# butter-test.net
KiCad netlist of a schematic drawn in EAGLE
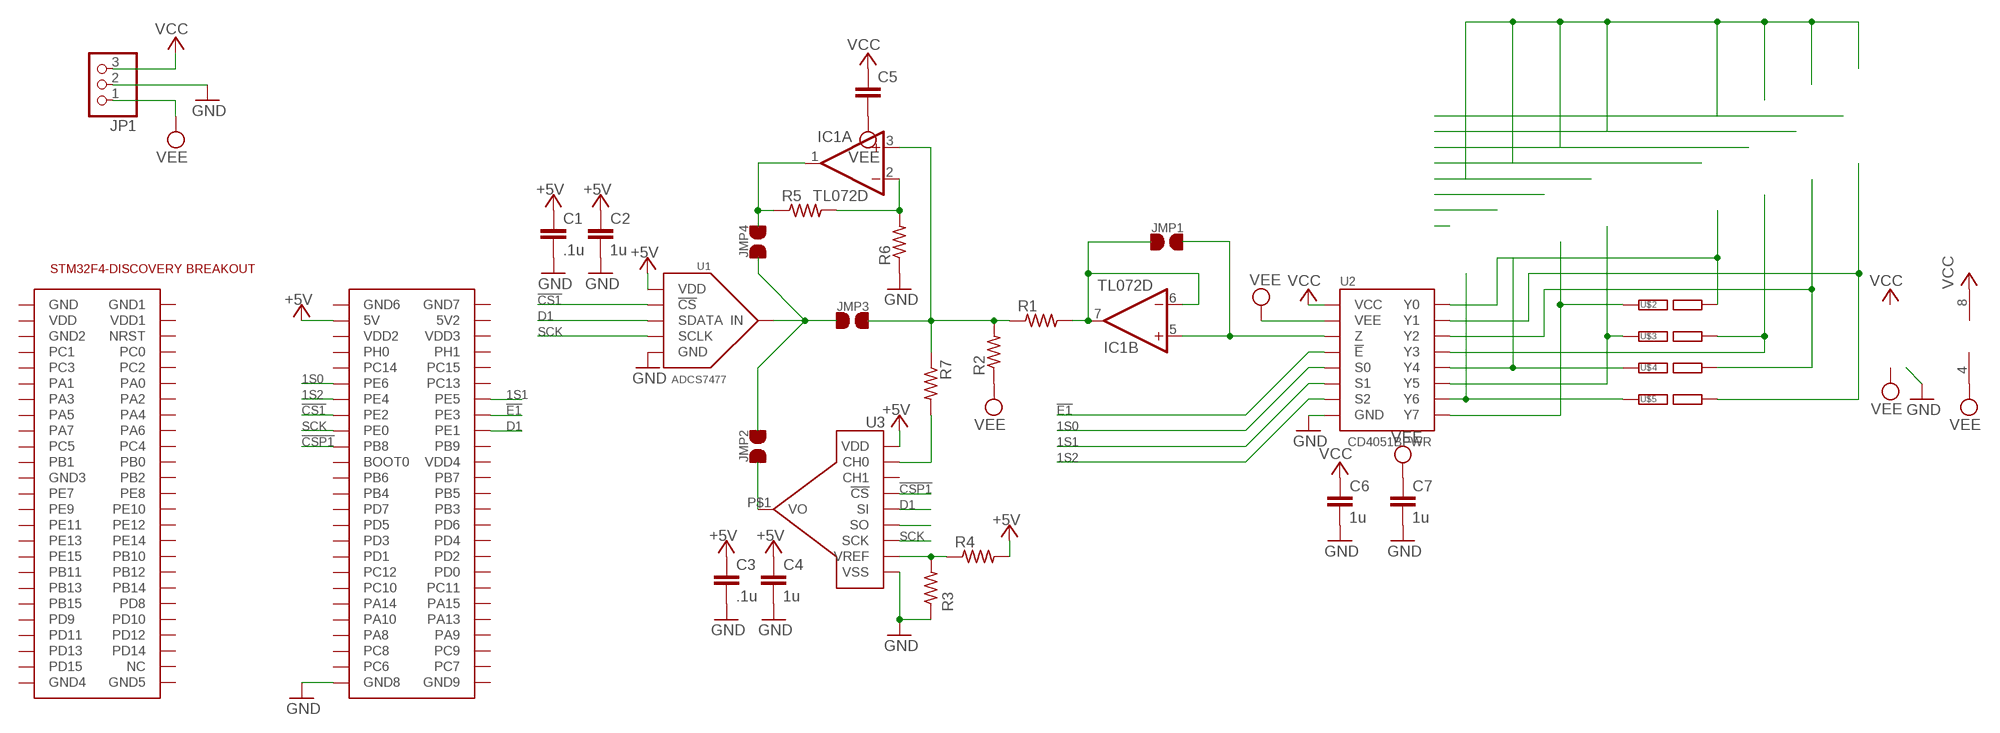
[diagram p0: schematic, sheet 1]

(export (version "E")
  (design (tool "Eeschema 10.0.6"))
  (components
    (comp (ref "C1")
      (value ".1u")
      (footprint "eagle-import:C0805")
      (libsource (lib "eagle-import") (part "C-EUC0805"))
    )
    (comp (ref "C2")
      (value "1u")
      (footprint "eagle-import:C0805")
      (libsource (lib "eagle-import") (part "C-EUC0805"))
    )
    (comp (ref "C3")
      (value ".1u")
      (footprint "eagle-import:C0805")
      (libsource (lib "eagle-import") (part "C-EUC0805"))
    )
    (comp (ref "C4")
      (value "1u")
      (footprint "eagle-import:C0805")
      (libsource (lib "eagle-import") (part "C-EUC0805"))
    )
    (comp (ref "C5")
      (value "C-EUC0805")
      (footprint "eagle-import:C0805")
      (libsource (lib "eagle-import") (part "C-EUC0805"))
    )
    (comp (ref "C6")
      (value "1u")
      (footprint "eagle-import:C0805")
      (libsource (lib "eagle-import") (part "C-EUC0805"))
    )
    (comp (ref "C7")
      (value "1u")
      (footprint "eagle-import:C0805")
      (libsource (lib "eagle-import") (part "C-EUC0805"))
    )
    (comp (ref "IC1")
      (value "TL072D")
      (footprint "eagle-import:SO08")
      (libsource (lib "eagle-import") (part "TL072D"))
    )
    (comp (ref "JMP1")
      (value "JMP")
      (footprint "eagle-import:JMP")
      (libsource (lib "eagle-import") (part "JMP"))
    )
    (comp (ref "JMP2")
      (value "JMP")
      (footprint "eagle-import:JMP")
      (libsource (lib "eagle-import") (part "JMP"))
    )
    (comp (ref "JMP3")
      (value "JMP")
      (footprint "eagle-import:JMP")
      (libsource (lib "eagle-import") (part "JMP"))
    )
    (comp (ref "JMP4")
      (value "JMP")
      (footprint "eagle-import:JMP")
      (libsource (lib "eagle-import") (part "JMP"))
    )
    (comp (ref "JP1")
      (value "PINHD-1X3")
      (footprint "eagle-import:1X03")
      (libsource (lib "eagle-import") (part "PINHD-1X3"))
    )
    (comp (ref "R1")
      (value "R-US_R0603")
      (footprint "eagle-import:R0603")
      (libsource (lib "eagle-import") (part "R-US_R0603"))
    )
    (comp (ref "R2")
      (value "R-US_R0603")
      (footprint "eagle-import:R0603")
      (libsource (lib "eagle-import") (part "R-US_R0603"))
    )
    (comp (ref "R3")
      (value "R-US_R0603")
      (footprint "eagle-import:R0603")
      (libsource (lib "eagle-import") (part "R-US_R0603"))
    )
    (comp (ref "R4")
      (value "R-US_R0603")
      (footprint "eagle-import:R0603")
      (libsource (lib "eagle-import") (part "R-US_R0603"))
    )
    (comp (ref "R5")
      (value "R-US_R0603")
      (footprint "eagle-import:R0603")
      (libsource (lib "eagle-import") (part "R-US_R0603"))
    )
    (comp (ref "R6")
      (value "R-US_R0603")
      (footprint "eagle-import:R0603")
      (libsource (lib "eagle-import") (part "R-US_R0603"))
    )
    (comp (ref "R7")
      (value "R-US_R0603")
      (footprint "eagle-import:R0603")
      (libsource (lib "eagle-import") (part "R-US_R0603"))
    )
    (comp (ref "U$1")
      (value "STM32F4-DISCOVERY")
      (footprint "eagle-import:STM32F4-DISCOVERY")
      (libsource (lib "eagle-import") (part "STM32F4-DISCOVERY"))
    )
    (comp (ref "U$2")
      (value "RAILSEP")
      (footprint "eagle-import:RAIL")
      (libsource (lib "eagle-import") (part "RAILSEP"))
    )
    (comp (ref "U$3")
      (value "RAILSEP")
      (footprint "eagle-import:RAIL")
      (libsource (lib "eagle-import") (part "RAILSEP"))
    )
    (comp (ref "U$4")
      (value "RAILSEP")
      (footprint "eagle-import:RAIL")
      (libsource (lib "eagle-import") (part "RAILSEP"))
    )
    (comp (ref "U$5")
      (value "RAILSEP")
      (footprint "eagle-import:RAIL")
      (libsource (lib "eagle-import") (part "RAILSEP"))
    )
    (comp (ref "U1")
      (value "ADCS7477")
      (footprint "eagle-import:SOT-23-6")
      (libsource (lib "eagle-import") (part "ADCS7477"))
    )
    (comp (ref "U2")
      (value "CD4051BPWR")
      (footprint "eagle-import:TSSOP-16")
      (libsource (lib "eagle-import") (part "CD4051BPWR"))
    )
    (comp (ref "U3")
      (value "MCP6S93")
      (footprint "eagle-import:MSOP-10")
      (libsource (lib "eagle-import") (part "MCP6S93"))
    )
  )
  (nets
    (net (code "1") (name "+5V") (class "Default")
      (node (ref "C1") (pin "1") (pinfunction "1_1") (pintype "passive"))
      (node (ref "C2") (pin "1") (pinfunction "1_1") (pintype "passive"))
      (node (ref "C3") (pin "1") (pinfunction "1_1") (pintype "passive"))
      (node (ref "C4") (pin "1") (pinfunction "1_1") (pintype "passive"))
      (node (ref "R4") (pin "2") (pinfunction "2_2") (pintype "passive"))
      (node (ref "U$1") (pin "P$53") (pinfunction "5V_P$53") (pintype "bidirectional"))
      (node (ref "U1") (pin "P$1") (pinfunction "VDD_P$1") (pintype "bidirectional"))
      (node (ref "U3") (pin "P$10") (pinfunction "VDD_P$10") (pintype "bidirectional"))
    )
    (net (code "2") (name "/1S0") (class "Default")
      (node (ref "U$1") (pin "P$61") (pinfunction "PE6_P$61") (pintype "bidirectional"))
      (node (ref "U2") (pin "P$11") (pinfunction "S0_P$11") (pintype "bidirectional"))
    )
    (net (code "3") (name "/1S1") (class "Default")
      (node (ref "U$1") (pin "P$64") (pinfunction "PE5_P$64") (pintype "bidirectional"))
      (node (ref "U2") (pin "P$10") (pinfunction "S1_P$10") (pintype "bidirectional"))
    )
    (net (code "4") (name "/1S2") (class "Default")
      (node (ref "U$1") (pin "P$63") (pinfunction "PE4_P$63") (pintype "bidirectional"))
      (node (ref "U2") (pin "P$9") (pinfunction "S2_P$9") (pintype "bidirectional"))
    )
    (net (code "5") (name "/D1") (class "Default")
      (node (ref "U$1") (pin "P$68") (pinfunction "PE1_P$68") (pintype "bidirectional"))
      (node (ref "U1") (pin "P$5") (pinfunction "SDATA_P$5") (pintype "bidirectional"))
      (node (ref "U3") (pin "P$7") (pinfunction "SI_P$7") (pintype "bidirectional"))
    )
    (net (code "6") (name "/SCK") (class "Default")
      (node (ref "U$1") (pin "P$67") (pinfunction "PE0_P$67") (pintype "bidirectional"))
      (node (ref "U1") (pin "P$4") (pinfunction "SCLK_P$4") (pintype "bidirectional"))
      (node (ref "U3") (pin "P$9") (pinfunction "SCK_P$9") (pintype "bidirectional"))
    )
    (net (code "7") (name "/~{CS1}") (class "Default")
      (node (ref "U$1") (pin "P$65") (pinfunction "PE2_P$65") (pintype "bidirectional"))
      (node (ref "U1") (pin "P$6") (pinfunction "~{CS}_P$6") (pintype "bidirectional"))
    )
    (net (code "8") (name "/~{CSP1}") (class "Default")
      (node (ref "U$1") (pin "P$69") (pinfunction "PB8_P$69") (pintype "bidirectional"))
      (node (ref "U3") (pin "P$6") (pinfunction "~{CS}_P$6") (pintype "bidirectional"))
    )
    (net (code "9") (name "/~{E1}") (class "Default")
      (node (ref "U$1") (pin "P$66") (pinfunction "PE3_P$66") (pintype "bidirectional"))
      (node (ref "U2") (pin "P$6") (pinfunction "~{E}_P$6") (pintype "bidirectional"))
    )
    (net (code "10") (name "GND") (class "Default")
      (node (ref "C1") (pin "2") (pinfunction "2_2") (pintype "passive"))
      (node (ref "C2") (pin "2") (pinfunction "2_2") (pintype "passive"))
      (node (ref "C3") (pin "2") (pinfunction "2_2") (pintype "passive"))
      (node (ref "C4") (pin "2") (pinfunction "2_2") (pintype "passive"))
      (node (ref "C6") (pin "2") (pinfunction "2_2") (pintype "passive"))
      (node (ref "C7") (pin "2") (pinfunction "2_2") (pintype "passive"))
      (node (ref "JP1") (pin "2") (pinfunction "2_2") (pintype "passive"))
      (node (ref "R3") (pin "1") (pinfunction "1_1") (pintype "passive"))
      (node (ref "R6") (pin "1") (pinfunction "1_1") (pintype "passive"))
      (node (ref "U$1") (pin "P$99") (pinfunction "GND8_P$99") (pintype "bidirectional"))
      (node (ref "U1") (pin "P$2") (pinfunction "GND_P$2") (pintype "bidirectional"))
      (node (ref "U2") (pin "P$8") (pinfunction "GND_P$8") (pintype "bidirectional"))
      (node (ref "U3") (pin "P$5") (pinfunction "VSS_P$5") (pintype "bidirectional"))
    )
    (net (code "11") (name "Net-(IC1A-+IN)") (class "Default")
      (node (ref "IC1") (pin "3") (pinfunction "+IN_3") (pintype "input"))
      (node (ref "JMP3") (pin "P$2") (pinfunction "P$2_P$2") (pintype "bidirectional"))
      (node (ref "R1") (pin "1") (pinfunction "1_1") (pintype "passive"))
      (node (ref "R2") (pin "2") (pinfunction "2_2") (pintype "passive"))
      (node (ref "R7") (pin "1") (pinfunction "1_1") (pintype "passive"))
    )
    (net (code "12") (name "Net-(IC1A--IN)") (class "Default")
      (node (ref "IC1") (pin "2") (pinfunction "-IN_2") (pintype "input"))
      (node (ref "R5") (pin "2") (pinfunction "2_2") (pintype "passive"))
      (node (ref "R6") (pin "2") (pinfunction "2_2") (pintype "passive"))
    )
    (net (code "13") (name "Net-(IC1A-OUT)") (class "Default")
      (node (ref "IC1") (pin "1") (pinfunction "OUT_1") (pintype "output"))
      (node (ref "JMP4") (pin "P$2") (pinfunction "P$2_P$2") (pintype "bidirectional"))
      (node (ref "R5") (pin "1") (pinfunction "1_1") (pintype "passive"))
    )
    (net (code "14") (name "Net-(IC1B-+IN)") (class "Default")
      (node (ref "IC1") (pin "5") (pinfunction "+IN_5") (pintype "input"))
      (node (ref "JMP1") (pin "P$2") (pinfunction "P$2_P$2") (pintype "bidirectional"))
      (node (ref "U2") (pin "P$3") (pinfunction "Z_P$3") (pintype "bidirectional"))
    )
    (net (code "15") (name "Net-(IC1B--IN)") (class "Default")
      (node (ref "IC1") (pin "6") (pinfunction "-IN_6") (pintype "input"))
      (node (ref "IC1") (pin "7") (pinfunction "OUT_7") (pintype "output"))
      (node (ref "JMP1") (pin "P$1") (pinfunction "P$1_P$1") (pintype "bidirectional"))
      (node (ref "R1") (pin "2") (pinfunction "2_2") (pintype "passive"))
    )
    (net (code "16") (name "Net-(U$2-L)") (class "Default")
      (node (ref "U$2") (pin "P$L") (pinfunction "L_P$L") (pintype "bidirectional"))
      (node (ref "U2") (pin "P$4") (pinfunction "Y7_P$4") (pintype "bidirectional"))
    )
    (net (code "17") (name "Net-(U$2-R)") (class "Default")
      (node (ref "U$2") (pin "P$R") (pinfunction "R_P$R") (pintype "bidirectional"))
      (node (ref "U2") (pin "P$13") (pinfunction "Y0_P$13") (pintype "bidirectional"))
    )
    (net (code "18") (name "Net-(U$3-L)") (class "Default")
      (node (ref "U$3") (pin "P$L") (pinfunction "L_P$L") (pintype "bidirectional"))
      (node (ref "U2") (pin "P$5") (pinfunction "Y5_P$5") (pintype "bidirectional"))
    )
    (net (code "19") (name "Net-(U$3-R)") (class "Default")
      (node (ref "U$3") (pin "P$R") (pinfunction "R_P$R") (pintype "bidirectional"))
      (node (ref "U2") (pin "P$12") (pinfunction "Y3_P$12") (pintype "bidirectional"))
    )
    (net (code "20") (name "Net-(U$4-L)") (class "Default")
      (node (ref "U$4") (pin "P$L") (pinfunction "L_P$L") (pintype "bidirectional"))
      (node (ref "U2") (pin "P$1") (pinfunction "Y4_P$1") (pintype "bidirectional"))
    )
    (net (code "21") (name "Net-(U$4-R)") (class "Default")
      (node (ref "U$4") (pin "P$R") (pinfunction "R_P$R") (pintype "bidirectional"))
      (node (ref "U2") (pin "P$15") (pinfunction "Y2_P$15") (pintype "bidirectional"))
    )
    (net (code "22") (name "Net-(U$5-L)") (class "Default")
      (node (ref "U$5") (pin "P$L") (pinfunction "L_P$L") (pintype "bidirectional"))
      (node (ref "U2") (pin "P$2") (pinfunction "Y6_P$2") (pintype "bidirectional"))
    )
    (net (code "23") (name "Net-(U$5-R)") (class "Default")
      (node (ref "U$5") (pin "P$R") (pinfunction "R_P$R") (pintype "bidirectional"))
      (node (ref "U2") (pin "P$14") (pinfunction "Y1_P$14") (pintype "bidirectional"))
    )
    (net (code "24") (name "Net-(U1-IN)") (class "Default")
      (node (ref "JMP2") (pin "P$2") (pinfunction "P$2_P$2") (pintype "bidirectional"))
      (node (ref "JMP3") (pin "P$1") (pinfunction "P$1_P$1") (pintype "bidirectional"))
      (node (ref "JMP4") (pin "P$1") (pinfunction "P$1_P$1") (pintype "bidirectional"))
      (node (ref "U1") (pin "P$3") (pinfunction "IN_P$3") (pintype "bidirectional"))
    )
    (net (code "25") (name "Net-(U3-CH0)") (class "Default")
      (node (ref "R7") (pin "2") (pinfunction "2_2") (pintype "passive"))
      (node (ref "U3") (pin "P$2") (pinfunction "CH0_P$2") (pintype "bidirectional"))
    )
    (net (code "26") (name "Net-(U3-VO)") (class "Default")
      (node (ref "JMP2") (pin "P$1") (pinfunction "P$1_P$1") (pintype "bidirectional"))
      (node (ref "U3") (pin "P$1") (pinfunction "VO_P$1") (pintype "bidirectional"))
    )
    (net (code "27") (name "Net-(U3-VREF)") (class "Default")
      (node (ref "R3") (pin "2") (pinfunction "2_2") (pintype "passive"))
      (node (ref "R4") (pin "1") (pinfunction "1_1") (pintype "passive"))
      (node (ref "U3") (pin "P$4") (pinfunction "VREF_P$4") (pintype "bidirectional"))
    )
    (net (code "28") (name "VCC") (class "Default")
      (node (ref "C5") (pin "1") (pinfunction "1_1") (pintype "passive"))
      (node (ref "C6") (pin "1") (pinfunction "1_1") (pintype "passive"))
      (node (ref "IC1") (pin "8") (pinfunction "V+_8") (pintype "power_in"))
      (node (ref "JP1") (pin "3") (pinfunction "3_3") (pintype "passive"))
      (node (ref "U2") (pin "P$16") (pinfunction "VCC_P$16") (pintype "bidirectional"))
    )
    (net (code "29") (name "VEE") (class "Default")
      (node (ref "C5") (pin "2") (pinfunction "2_2") (pintype "passive"))
      (node (ref "C7") (pin "1") (pinfunction "1_1") (pintype "passive"))
      (node (ref "IC1") (pin "4") (pinfunction "V-_4") (pintype "power_in"))
      (node (ref "JP1") (pin "1") (pinfunction "1_1") (pintype "passive"))
      (node (ref "R2") (pin "1") (pinfunction "1_1") (pintype "passive"))
      (node (ref "U2") (pin "P$7") (pinfunction "VEE_P$7") (pintype "bidirectional"))
    )
    (net (code "30") (name "unconnected-(U$1-5V2-PadP$54)") (class "Default")
      (node (ref "U$1") (pin "P$54") (pinfunction "5V2_P$54") (pintype "bidirectional"))
    )
    (net (code "31") (name "unconnected-(U$1-BOOT0-PadP$71)") (class "Default")
      (node (ref "U$1") (pin "P$71") (pinfunction "BOOT0_P$71") (pintype "bidirectional"))
    )
    (net (code "32") (name "unconnected-(U$1-GND-PadP$1)") (class "Default")
      (node (ref "U$1") (pin "P$1") (pinfunction "GND_P$1") (pintype "bidirectional"))
    )
    (net (code "33") (name "unconnected-(U$1-GND1-PadP$2)") (class "Default")
      (node (ref "U$1") (pin "P$2") (pinfunction "GND1_P$2") (pintype "bidirectional"))
    )
    (net (code "34") (name "unconnected-(U$1-GND2-PadP$5)") (class "Default")
      (node (ref "U$1") (pin "P$5") (pinfunction "GND2_P$5") (pintype "bidirectional"))
    )
    (net (code "35") (name "unconnected-(U$1-GND3-PadP$23)") (class "Default")
      (node (ref "U$1") (pin "P$23") (pinfunction "GND3_P$23") (pintype "bidirectional"))
    )
    (net (code "36") (name "unconnected-(U$1-GND4-PadP$49)") (class "Default")
      (node (ref "U$1") (pin "P$49") (pinfunction "GND4_P$49") (pintype "bidirectional"))
    )
    (net (code "37") (name "unconnected-(U$1-GND5-PadP$50)") (class "Default")
      (node (ref "U$1") (pin "P$50") (pinfunction "GND5_P$50") (pintype "bidirectional"))
    )
    (net (code "38") (name "unconnected-(U$1-GND6-PadP$51)") (class "Default")
      (node (ref "U$1") (pin "P$51") (pinfunction "GND6_P$51") (pintype "bidirectional"))
    )
    (net (code "39") (name "unconnected-(U$1-GND7-PadP$52)") (class "Default")
      (node (ref "U$1") (pin "P$52") (pinfunction "GND7_P$52") (pintype "bidirectional"))
    )
    (net (code "40") (name "unconnected-(U$1-GND9-PadP$100)") (class "Default")
      (node (ref "U$1") (pin "P$100") (pinfunction "GND9_P$100") (pintype "bidirectional"))
    )
    (net (code "41") (name "unconnected-(U$1-NC-PadP$48)") (class "Default")
      (node (ref "U$1") (pin "P$48") (pinfunction "NC_P$48") (pintype "bidirectional"))
    )
    (net (code "42") (name "unconnected-(U$1-NRST-PadP$6)") (class "Default")
      (node (ref "U$1") (pin "P$6") (pinfunction "NRST_P$6") (pintype "bidirectional"))
    )
    (net (code "43") (name "unconnected-(U$1-PA0-PadP$12)") (class "Default")
      (node (ref "U$1") (pin "P$12") (pinfunction "PA0_P$12") (pintype "bidirectional"))
    )
    (net (code "44") (name "unconnected-(U$1-PA1-PadP$11)") (class "Default")
      (node (ref "U$1") (pin "P$11") (pinfunction "PA1_P$11") (pintype "bidirectional"))
    )
    (net (code "45") (name "unconnected-(U$1-PA2-PadP$14)") (class "Default")
      (node (ref "U$1") (pin "P$14") (pinfunction "PA2_P$14") (pintype "bidirectional"))
    )
    (net (code "46") (name "unconnected-(U$1-PA3-PadP$13)") (class "Default")
      (node (ref "U$1") (pin "P$13") (pinfunction "PA3_P$13") (pintype "bidirectional"))
    )
    (net (code "47") (name "unconnected-(U$1-PA4-PadP$16)") (class "Default")
      (node (ref "U$1") (pin "P$16") (pinfunction "PA4_P$16") (pintype "bidirectional"))
    )
    (net (code "48") (name "unconnected-(U$1-PA5-PadP$15)") (class "Default")
      (node (ref "U$1") (pin "P$15") (pinfunction "PA5_P$15") (pintype "bidirectional"))
    )
    (net (code "49") (name "unconnected-(U$1-PA6-PadP$18)") (class "Default")
      (node (ref "U$1") (pin "P$18") (pinfunction "PA6_P$18") (pintype "bidirectional"))
    )
    (net (code "50") (name "unconnected-(U$1-PA7-PadP$17)") (class "Default")
      (node (ref "U$1") (pin "P$17") (pinfunction "PA7_P$17") (pintype "bidirectional"))
    )
    (net (code "51") (name "unconnected-(U$1-PA8-PadP$93)") (class "Default")
      (node (ref "U$1") (pin "P$93") (pinfunction "PA8_P$93") (pintype "bidirectional"))
    )
    (net (code "52") (name "unconnected-(U$1-PA9-PadP$94)") (class "Default")
      (node (ref "U$1") (pin "P$94") (pinfunction "PA9_P$94") (pintype "bidirectional"))
    )
    (net (code "53") (name "unconnected-(U$1-PA10-PadP$91)") (class "Default")
      (node (ref "U$1") (pin "P$91") (pinfunction "PA10_P$91") (pintype "bidirectional"))
    )
    (net (code "54") (name "unconnected-(U$1-PA13-PadP$92)") (class "Default")
      (node (ref "U$1") (pin "P$92") (pinfunction "PA13_P$92") (pintype "bidirectional"))
    )
    (net (code "55") (name "unconnected-(U$1-PA14-PadP$89)") (class "Default")
      (node (ref "U$1") (pin "P$89") (pinfunction "PA14_P$89") (pintype "bidirectional"))
    )
    (net (code "56") (name "unconnected-(U$1-PA15-PadP$90)") (class "Default")
      (node (ref "U$1") (pin "P$90") (pinfunction "PA15_P$90") (pintype "bidirectional"))
    )
    (net (code "57") (name "unconnected-(U$1-PB0-PadP$22)") (class "Default")
      (node (ref "U$1") (pin "P$22") (pinfunction "PB0_P$22") (pintype "bidirectional"))
    )
    (net (code "58") (name "unconnected-(U$1-PB1-PadP$21)") (class "Default")
      (node (ref "U$1") (pin "P$21") (pinfunction "PB1_P$21") (pintype "bidirectional"))
    )
    (net (code "59") (name "unconnected-(U$1-PB2-PadP$24)") (class "Default")
      (node (ref "U$1") (pin "P$24") (pinfunction "PB2_P$24") (pintype "bidirectional"))
    )
    (net (code "60") (name "unconnected-(U$1-PB3-PadP$78)") (class "Default")
      (node (ref "U$1") (pin "P$78") (pinfunction "PB3_P$78") (pintype "bidirectional"))
    )
    (net (code "61") (name "unconnected-(U$1-PB4-PadP$75)") (class "Default")
      (node (ref "U$1") (pin "P$75") (pinfunction "PB4_P$75") (pintype "bidirectional"))
    )
    (net (code "62") (name "unconnected-(U$1-PB5-PadP$76)") (class "Default")
      (node (ref "U$1") (pin "P$76") (pinfunction "PB5_P$76") (pintype "bidirectional"))
    )
    (net (code "63") (name "unconnected-(U$1-PB6-PadP$73)") (class "Default")
      (node (ref "U$1") (pin "P$73") (pinfunction "PB6_P$73") (pintype "bidirectional"))
    )
    (net (code "64") (name "unconnected-(U$1-PB7-PadP$74)") (class "Default")
      (node (ref "U$1") (pin "P$74") (pinfunction "PB7_P$74") (pintype "bidirectional"))
    )
    (net (code "65") (name "unconnected-(U$1-PB9-PadP$70)") (class "Default")
      (node (ref "U$1") (pin "P$70") (pinfunction "PB9_P$70") (pintype "bidirectional"))
    )
    (net (code "66") (name "unconnected-(U$1-PB10-PadP$34)") (class "Default")
      (node (ref "U$1") (pin "P$34") (pinfunction "PB10_P$34") (pintype "bidirectional"))
    )
    (net (code "67") (name "unconnected-(U$1-PB11-PadP$35)") (class "Default")
      (node (ref "U$1") (pin "P$35") (pinfunction "PB11_P$35") (pintype "bidirectional"))
    )
    (net (code "68") (name "unconnected-(U$1-PB12-PadP$36)") (class "Default")
      (node (ref "U$1") (pin "P$36") (pinfunction "PB12_P$36") (pintype "bidirectional"))
    )
    (net (code "69") (name "unconnected-(U$1-PB13-PadP$37)") (class "Default")
      (node (ref "U$1") (pin "P$37") (pinfunction "PB13_P$37") (pintype "bidirectional"))
    )
    (net (code "70") (name "unconnected-(U$1-PB14-PadP$38)") (class "Default")
      (node (ref "U$1") (pin "P$38") (pinfunction "PB14_P$38") (pintype "bidirectional"))
    )
    (net (code "71") (name "unconnected-(U$1-PB15-PadP$39)") (class "Default")
      (node (ref "U$1") (pin "P$39") (pinfunction "PB15_P$39") (pintype "bidirectional"))
    )
    (net (code "72") (name "unconnected-(U$1-PC0-PadP$8)") (class "Default")
      (node (ref "U$1") (pin "P$8") (pinfunction "PC0_P$8") (pintype "bidirectional"))
    )
    (net (code "73") (name "unconnected-(U$1-PC1-PadP$7)") (class "Default")
      (node (ref "U$1") (pin "P$7") (pinfunction "PC1_P$7") (pintype "bidirectional"))
    )
    (net (code "74") (name "unconnected-(U$1-PC2-PadP$10)") (class "Default")
      (node (ref "U$1") (pin "P$10") (pinfunction "PC2_P$10") (pintype "bidirectional"))
    )
    (net (code "75") (name "unconnected-(U$1-PC3-PadP$9)") (class "Default")
      (node (ref "U$1") (pin "P$9") (pinfunction "PC3_P$9") (pintype "bidirectional"))
    )
    (net (code "76") (name "unconnected-(U$1-PC4-PadP$20)") (class "Default")
      (node (ref "U$1") (pin "P$20") (pinfunction "PC4_P$20") (pintype "bidirectional"))
    )
    (net (code "77") (name "unconnected-(U$1-PC5-PadP$19)") (class "Default")
      (node (ref "U$1") (pin "P$19") (pinfunction "PC5_P$19") (pintype "bidirectional"))
    )
    (net (code "78") (name "unconnected-(U$1-PC6-PadP$97)") (class "Default")
      (node (ref "U$1") (pin "P$97") (pinfunction "PC6_P$97") (pintype "bidirectional"))
    )
    (net (code "79") (name "unconnected-(U$1-PC7-PadP$98)") (class "Default")
      (node (ref "U$1") (pin "P$98") (pinfunction "PC7_P$98") (pintype "bidirectional"))
    )
    (net (code "80") (name "unconnected-(U$1-PC8-PadP$95)") (class "Default")
      (node (ref "U$1") (pin "P$95") (pinfunction "PC8_P$95") (pintype "bidirectional"))
    )
    (net (code "81") (name "unconnected-(U$1-PC9-PadP$96)") (class "Default")
      (node (ref "U$1") (pin "P$96") (pinfunction "PC9_P$96") (pintype "bidirectional"))
    )
    (net (code "82") (name "unconnected-(U$1-PC10-PadP$87)") (class "Default")
      (node (ref "U$1") (pin "P$87") (pinfunction "PC10_P$87") (pintype "bidirectional"))
    )
    (net (code "83") (name "unconnected-(U$1-PC11-PadP$88)") (class "Default")
      (node (ref "U$1") (pin "P$88") (pinfunction "PC11_P$88") (pintype "bidirectional"))
    )
    (net (code "84") (name "unconnected-(U$1-PC12-PadP$85)") (class "Default")
      (node (ref "U$1") (pin "P$85") (pinfunction "PC12_P$85") (pintype "bidirectional"))
    )
    (net (code "85") (name "unconnected-(U$1-PC13-PadP$62)") (class "Default")
      (node (ref "U$1") (pin "P$62") (pinfunction "PC13_P$62") (pintype "bidirectional"))
    )
    (net (code "86") (name "unconnected-(U$1-PC14-PadP$59)") (class "Default")
      (node (ref "U$1") (pin "P$59") (pinfunction "PC14_P$59") (pintype "bidirectional"))
    )
    (net (code "87") (name "unconnected-(U$1-PC15-PadP$60)") (class "Default")
      (node (ref "U$1") (pin "P$60") (pinfunction "PC15_P$60") (pintype "bidirectional"))
    )
    (net (code "88") (name "unconnected-(U$1-PD0-PadP$86)") (class "Default")
      (node (ref "U$1") (pin "P$86") (pinfunction "PD0_P$86") (pintype "bidirectional"))
    )
    (net (code "89") (name "unconnected-(U$1-PD1-PadP$83)") (class "Default")
      (node (ref "U$1") (pin "P$83") (pinfunction "PD1_P$83") (pintype "bidirectional"))
    )
    (net (code "90") (name "unconnected-(U$1-PD2-PadP$84)") (class "Default")
      (node (ref "U$1") (pin "P$84") (pinfunction "PD2_P$84") (pintype "bidirectional"))
    )
    (net (code "91") (name "unconnected-(U$1-PD3-PadP$81)") (class "Default")
      (node (ref "U$1") (pin "P$81") (pinfunction "PD3_P$81") (pintype "bidirectional"))
    )
    (net (code "92") (name "unconnected-(U$1-PD4-PadP$82)") (class "Default")
      (node (ref "U$1") (pin "P$82") (pinfunction "PD4_P$82") (pintype "bidirectional"))
    )
    (net (code "93") (name "unconnected-(U$1-PD5-PadP$79)") (class "Default")
      (node (ref "U$1") (pin "P$79") (pinfunction "PD5_P$79") (pintype "bidirectional"))
    )
    (net (code "94") (name "unconnected-(U$1-PD6-PadP$80)") (class "Default")
      (node (ref "U$1") (pin "P$80") (pinfunction "PD6_P$80") (pintype "bidirectional"))
    )
    (net (code "95") (name "unconnected-(U$1-PD7-PadP$77)") (class "Default")
      (node (ref "U$1") (pin "P$77") (pinfunction "PD7_P$77") (pintype "bidirectional"))
    )
    (net (code "96") (name "unconnected-(U$1-PD8-PadP$40)") (class "Default")
      (node (ref "U$1") (pin "P$40") (pinfunction "PD8_P$40") (pintype "bidirectional"))
    )
    (net (code "97") (name "unconnected-(U$1-PD9-PadP$41)") (class "Default")
      (node (ref "U$1") (pin "P$41") (pinfunction "PD9_P$41") (pintype "bidirectional"))
    )
    (net (code "98") (name "unconnected-(U$1-PD10-PadP$42)") (class "Default")
      (node (ref "U$1") (pin "P$42") (pinfunction "PD10_P$42") (pintype "bidirectional"))
    )
    (net (code "99") (name "unconnected-(U$1-PD11-PadP$43)") (class "Default")
      (node (ref "U$1") (pin "P$43") (pinfunction "PD11_P$43") (pintype "bidirectional"))
    )
    (net (code "100") (name "unconnected-(U$1-PD12-PadP$44)") (class "Default")
      (node (ref "U$1") (pin "P$44") (pinfunction "PD12_P$44") (pintype "bidirectional"))
    )
    (net (code "101") (name "unconnected-(U$1-PD13-PadP$45)") (class "Default")
      (node (ref "U$1") (pin "P$45") (pinfunction "PD13_P$45") (pintype "bidirectional"))
    )
    (net (code "102") (name "unconnected-(U$1-PD14-PadP$46)") (class "Default")
      (node (ref "U$1") (pin "P$46") (pinfunction "PD14_P$46") (pintype "bidirectional"))
    )
    (net (code "103") (name "unconnected-(U$1-PD15-PadP$47)") (class "Default")
      (node (ref "U$1") (pin "P$47") (pinfunction "PD15_P$47") (pintype "bidirectional"))
    )
    (net (code "104") (name "unconnected-(U$1-PE7-PadP$25)") (class "Default")
      (node (ref "U$1") (pin "P$25") (pinfunction "PE7_P$25") (pintype "bidirectional"))
    )
    (net (code "105") (name "unconnected-(U$1-PE8-PadP$26)") (class "Default")
      (node (ref "U$1") (pin "P$26") (pinfunction "PE8_P$26") (pintype "bidirectional"))
    )
    (net (code "106") (name "unconnected-(U$1-PE9-PadP$27)") (class "Default")
      (node (ref "U$1") (pin "P$27") (pinfunction "PE9_P$27") (pintype "bidirectional"))
    )
    (net (code "107") (name "unconnected-(U$1-PE10-PadP$28)") (class "Default")
      (node (ref "U$1") (pin "P$28") (pinfunction "PE10_P$28") (pintype "bidirectional"))
    )
    (net (code "108") (name "unconnected-(U$1-PE11-PadP$29)") (class "Default")
      (node (ref "U$1") (pin "P$29") (pinfunction "PE11_P$29") (pintype "bidirectional"))
    )
    (net (code "109") (name "unconnected-(U$1-PE12-PadP$30)") (class "Default")
      (node (ref "U$1") (pin "P$30") (pinfunction "PE12_P$30") (pintype "bidirectional"))
    )
    (net (code "110") (name "unconnected-(U$1-PE13-PadP$31)") (class "Default")
      (node (ref "U$1") (pin "P$31") (pinfunction "PE13_P$31") (pintype "bidirectional"))
    )
    (net (code "111") (name "unconnected-(U$1-PE14-PadP$32)") (class "Default")
      (node (ref "U$1") (pin "P$32") (pinfunction "PE14_P$32") (pintype "bidirectional"))
    )
    (net (code "112") (name "unconnected-(U$1-PE15-PadP$33)") (class "Default")
      (node (ref "U$1") (pin "P$33") (pinfunction "PE15_P$33") (pintype "bidirectional"))
    )
    (net (code "113") (name "unconnected-(U$1-PH0-PadP$57)") (class "Default")
      (node (ref "U$1") (pin "P$57") (pinfunction "PH0_P$57") (pintype "bidirectional"))
    )
    (net (code "114") (name "unconnected-(U$1-PH1-PadP$58)") (class "Default")
      (node (ref "U$1") (pin "P$58") (pinfunction "PH1_P$58") (pintype "bidirectional"))
    )
    (net (code "115") (name "unconnected-(U$1-VDD-PadP$3)") (class "Default")
      (node (ref "U$1") (pin "P$3") (pinfunction "VDD_P$3") (pintype "bidirectional"))
    )
    (net (code "116") (name "unconnected-(U$1-VDD1-PadP$4)") (class "Default")
      (node (ref "U$1") (pin "P$4") (pinfunction "VDD1_P$4") (pintype "bidirectional"))
    )
    (net (code "117") (name "unconnected-(U$1-VDD2-PadP$55)") (class "Default")
      (node (ref "U$1") (pin "P$55") (pinfunction "VDD2_P$55") (pintype "bidirectional"))
    )
    (net (code "118") (name "unconnected-(U$1-VDD3-PadP$56)") (class "Default")
      (node (ref "U$1") (pin "P$56") (pinfunction "VDD3_P$56") (pintype "bidirectional"))
    )
    (net (code "119") (name "unconnected-(U$1-VDD4-PadP$72)") (class "Default")
      (node (ref "U$1") (pin "P$72") (pinfunction "VDD4_P$72") (pintype "bidirectional"))
    )
    (net (code "120") (name "unconnected-(U3-CH1-PadP$3)") (class "Default")
      (node (ref "U3") (pin "P$3") (pinfunction "CH1_P$3") (pintype "bidirectional"))
    )
    (net (code "121") (name "unconnected-(U3-SO-PadP$8)") (class "Default")
      (node (ref "U3") (pin "P$8") (pinfunction "SO_P$8") (pintype "bidirectional"))
    )
  )
)
